# Quad-RS232-1_0-RS232.net
KiCad netlist of a schematic drawn in Altium Designer
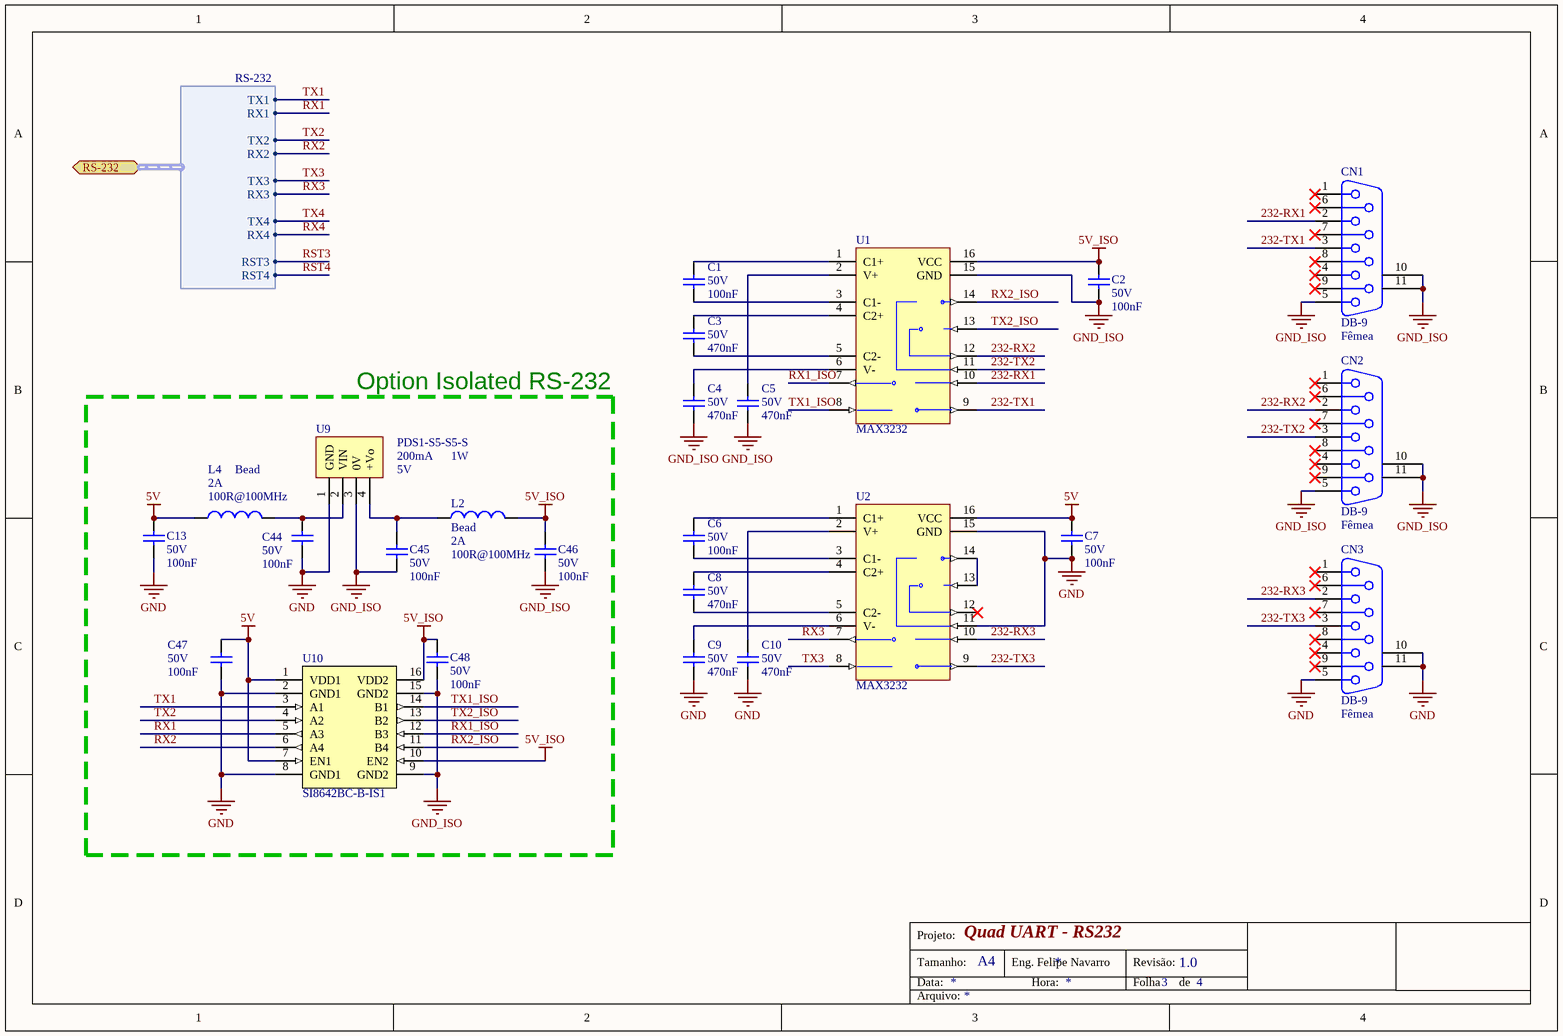
[diagram p0: Quad-RS232-1.0-RS232.SchDoc]

(export (version "E")
  (design (tool "Eeschema 10.0.6"))
  (components
    (comp (ref "C1")
      (value "100nF")
      (footprint "CC0603")
      (description "Capacitor (Semiconductor SIM Model)")
      (fields (field (name "TENSÃO") "50V") (field (name "Comment") "Capacitor Cerâmico"))
      (libsource (lib "NavarroCAP") (part "Cap 1uF 50V 0603 X5R"))
    )
    (comp (ref "C2")
      (value "100nF")
      (footprint "CC0603")
      (description "Capacitor (Semiconductor SIM Model)")
      (fields (field (name "TENSÃO") "50V") (field (name "Comment") "Capacitor Cerâmico"))
      (libsource (lib "NavarroCAP") (part "Cap 100nF 50V 0603 X7R"))
    )
    (comp (ref "C3")
      (value "470nF")
      (footprint "CC0603")
      (description "Capacitor (Semiconductor SIM Model)")
      (fields (field (name "TENSÃO") "50V") (field (name "Comment") "Capacitor Cerâmico"))
      (libsource (lib "NavarroCAP") (part "Cap 1uF 50V 0603 X5R"))
    )
    (comp (ref "C4")
      (value "470nF")
      (footprint "CC0603")
      (description "Capacitor (Semiconductor SIM Model)")
      (fields (field (name "TENSÃO") "50V") (field (name "Comment") "Capacitor Cerâmico"))
      (libsource (lib "NavarroCAP") (part "Cap 1uF 50V 0603 X5R"))
    )
    (comp (ref "C5")
      (value "470nF")
      (footprint "CC0603")
      (description "Capacitor (Semiconductor SIM Model)")
      (fields (field (name "TENSÃO") "50V") (field (name "Comment") "Capacitor Cerâmico"))
      (libsource (lib "NavarroCAP") (part "Cap 1uF 50V 0603 X5R"))
    )
    (comp (ref "C6")
      (value "100nF")
      (footprint "CC0603")
      (description "Capacitor (Semiconductor SIM Model)")
      (fields (field (name "TENSÃO") "50V") (field (name "Comment") "Capacitor Cerâmico"))
      (libsource (lib "NavarroCAP") (part "Cap 1uF 50V 0603 X5R"))
    )
    (comp (ref "C7")
      (value "100nF")
      (footprint "CC0603")
      (description "Capacitor (Semiconductor SIM Model)")
      (fields (field (name "TENSÃO") "50V") (field (name "Comment") "Capacitor Cerâmico"))
      (libsource (lib "NavarroCAP") (part "Cap 100nF 50V 0603 X7R"))
    )
    (comp (ref "C8")
      (value "470nF")
      (footprint "CC0603")
      (description "Capacitor (Semiconductor SIM Model)")
      (fields (field (name "TENSÃO") "50V") (field (name "Comment") "Capacitor Cerâmico"))
      (libsource (lib "NavarroCAP") (part "Cap 1uF 50V 0603 X5R"))
    )
    (comp (ref "C9")
      (value "470nF")
      (footprint "CC0603")
      (description "Capacitor (Semiconductor SIM Model)")
      (fields (field (name "TENSÃO") "50V") (field (name "Comment") "Capacitor Cerâmico"))
      (libsource (lib "NavarroCAP") (part "Cap 1uF 50V 0603 X5R"))
    )
    (comp (ref "C10")
      (value "470nF")
      (footprint "CC0603")
      (description "Capacitor (Semiconductor SIM Model)")
      (fields (field (name "TENSÃO") "50V") (field (name "Comment") "Capacitor Cerâmico"))
      (libsource (lib "NavarroCAP") (part "Cap 1uF 50V 0603 X5R"))
    )
    (comp (ref "C13")
      (value "100nF")
      (footprint "CC0603")
      (description "Capacitor (Semiconductor SIM Model)")
      (fields (field (name "TENSÃO") "50V") (field (name "Comment") "Capacitor Cerâmico"))
      (libsource (lib "NavarroCAP") (part "Cap 100nF 50V 0603 X7R"))
    )
    (comp (ref "C44")
      (value "100nF")
      (footprint "CC0603")
      (description "Capacitor (Semiconductor SIM Model)")
      (fields (field (name "TENSÃO") "50V") (field (name "Comment") "Capacitor Cerâmico"))
      (libsource (lib "NavarroCAP") (part "Cap 100nF 50V 0603 X7R"))
    )
    (comp (ref "C45")
      (value "100nF")
      (footprint "CC0603")
      (description "Capacitor (Semiconductor SIM Model)")
      (fields (field (name "TENSÃO") "50V") (field (name "Comment") "Capacitor Cerâmico"))
      (libsource (lib "NavarroCAP") (part "Cap 100nF 50V 0603 X7R"))
    )
    (comp (ref "C46")
      (value "100nF")
      (footprint "CC0603")
      (description "Capacitor (Semiconductor SIM Model)")
      (fields (field (name "TENSÃO") "50V") (field (name "Comment") "Capacitor Cerâmico"))
      (libsource (lib "NavarroCAP") (part "Cap 100nF 50V 0603 X7R"))
    )
    (comp (ref "C47")
      (value "100nF")
      (footprint "CC0603")
      (description "Capacitor (Semiconductor SIM Model)")
      (fields (field (name "TENSÃO") "50V") (field (name "Comment") "Capacitor Cerâmico"))
      (libsource (lib "NavarroCAP") (part "Cap 100nF 50V 0603 X7R"))
    )
    (comp (ref "C48")
      (value "100nF")
      (footprint "CC0603")
      (description "Capacitor (Semiconductor SIM Model)")
      (fields (field (name "TENSÃO") "50V") (field (name "Comment") "Capacitor Cerâmico"))
      (libsource (lib "NavarroCAP") (part "Cap 100nF 50V 0603 X7R"))
    )
    (comp (ref "CN1")
      (value "DB-9")
      (footprint "CONN DB9-F/H")
      (description "Receptacle Assembly, 9 Position, Right Angle")
      (fields (field (name "ALTIUM_VALUE") "Fêmea"))
      (libsource (lib "NavarroCON") (part "DB-9 Femea"))
    )
    (comp (ref "CN2")
      (value "DB-9")
      (footprint "CONN DB9-F/H")
      (description "Receptacle Assembly, 9 Position, Right Angle")
      (fields (field (name "ALTIUM_VALUE") "Fêmea"))
      (libsource (lib "NavarroCON") (part "DB-9 Femea"))
    )
    (comp (ref "CN3")
      (value "DB-9")
      (footprint "CONN DB9-F/H")
      (description "Receptacle Assembly, 9 Position, Right Angle")
      (fields (field (name "ALTIUM_VALUE") "Fêmea"))
      (libsource (lib "NavarroCON") (part "DB-9 Femea"))
    )
    (comp (ref "L2")
      (value "Bead")
      (footprint "CC0603")
      (fields (field (name "CORRENTE") "2A") (field (name "ALTIUM_VALUE") "100R@100MHz"))
      (libsource (lib "NavarroIND") (part "Bd 100R@100MHz 0603 2A"))
    )
    (comp (ref "L4")
      (value "Bead")
      (footprint "CC0603")
      (fields (field (name "CORRENTE") "2A") (field (name "ALTIUM_VALUE") "100R@100MHz"))
      (libsource (lib "NavarroIND") (part "Bd 100R@100MHz 0603 2A"))
    )
    (comp (ref "U1")
      (value "MAX3232")
      (footprint "SOIC-16N")
      (description "3.0V TO 5.5V, Low-Power, up to 1Mbps, True RS-232 Transceiver Using Four 0.1µF External Capacitor")
      (libsource (lib "Navarro") (part "MAX3232"))
    )
    (comp (ref "U2")
      (value "MAX3232")
      (footprint "SOIC-16N")
      (description "3.0V TO 5.5V, Low-Power, up to 1Mbps, True RS-232 Transceiver Using Four 0.1µF External Capacitor")
      (libsource (lib "Navarro") (part "MAX3232"))
    )
    (comp (ref "U9")
      (value "PDS1-S5-S5-S")
      (footprint "SIP-4N")
      (description "Fonte chaveada isolada")
      (fields (field (name "CORRENTE") "200mA") (field (name "POTÊNCIA") "1W") (field (name "TENSÃO") "5V"))
      (libsource (lib "Navarro") (part "Fonte PDS1-S5-S5-S"))
    )
    (comp (ref "U10")
      (value "SI8642BC-B-IS1")
      (footprint "SOIC-16N")
      (description "LOW-POWER QUAD-CHANNEL DIGITAL ISOLATOR")
      (libsource (lib "Navarro") (part "SI8642"))
    )
  )
  (nets
    (net (code "2") (name "/232-RX1") (class "Default")
      (node (ref "CN1") (pin "2") (pinfunction "2_2") (pintype "passive"))
      (node (ref "U1") (pin "10") (pinfunction "T2IN_10") (pintype "input"))
    )
    (net (code "3") (name "/232-RX2") (class "Default")
      (node (ref "CN2") (pin "2") (pinfunction "2_2") (pintype "passive"))
      (node (ref "U1") (pin "12") (pinfunction "R1OUT_12") (pintype "output"))
    )
    (net (code "4") (name "/232-RX3") (class "Default")
      (node (ref "CN3") (pin "2") (pinfunction "2_2") (pintype "passive"))
      (node (ref "U2") (pin "10") (pinfunction "T2IN_10") (pintype "input"))
    )
    (net (code "5") (name "/232-TX1") (class "Default")
      (node (ref "CN1") (pin "3") (pinfunction "3_3") (pintype "passive"))
      (node (ref "U1") (pin "9") (pinfunction "R2OUT_9") (pintype "output"))
    )
    (net (code "6") (name "/232-TX2") (class "Default")
      (node (ref "CN2") (pin "3") (pinfunction "3_3") (pintype "passive"))
      (node (ref "U1") (pin "11") (pinfunction "T1IN_11") (pintype "input"))
    )
    (net (code "7") (name "/232-TX3") (class "Default")
      (node (ref "CN3") (pin "3") (pinfunction "3_3") (pintype "passive"))
      (node (ref "U2") (pin "9") (pinfunction "R2OUT_9") (pintype "output"))
    )
    (net (code "10") (name "/RX1") (class "Default")
      (node (ref "U10") (pin "5") (pinfunction "A3_5") (pintype "output"))
    )
    (net (code "11") (name "/RX1_ISO") (class "Default")
      (node (ref "U1") (pin "7") (pinfunction "T2OUT_7") (pintype "output"))
      (node (ref "U10") (pin "12") (pinfunction "B3_12") (pintype "input"))
    )
    (net (code "12") (name "/RX2") (class "Default")
      (node (ref "U10") (pin "6") (pinfunction "A4_6") (pintype "output"))
    )
    (net (code "13") (name "/RX2_ISO") (class "Default")
      (node (ref "U1") (pin "14") (pinfunction "T1OUT_14") (pintype "output"))
      (node (ref "U10") (pin "11") (pinfunction "B4_11") (pintype "input"))
    )
    (net (code "14") (name "/RX3") (class "Default")
      (node (ref "U2") (pin "7") (pinfunction "T2OUT_7") (pintype "output"))
    )
    (net (code "16") (name "/TX1") (class "Default")
      (node (ref "U10") (pin "3") (pinfunction "A1_3") (pintype "input"))
    )
    (net (code "17") (name "/TX1_ISO") (class "Default")
      (node (ref "U1") (pin "8") (pinfunction "R2IN_8") (pintype "input"))
      (node (ref "U10") (pin "14") (pinfunction "B1_14") (pintype "output"))
    )
    (net (code "18") (name "/TX2") (class "Default")
      (node (ref "U10") (pin "4") (pinfunction "A2_4") (pintype "input"))
    )
    (net (code "19") (name "/TX2_ISO") (class "Default")
      (node (ref "U1") (pin "13") (pinfunction "R1IN_13") (pintype "input"))
      (node (ref "U10") (pin "13") (pinfunction "B2_13") (pintype "output"))
    )
    (net (code "20") (name "/TX3") (class "Default")
      (node (ref "U2") (pin "8") (pinfunction "R2IN_8") (pintype "input"))
    )
    (net (code "23") (name "5V") (class "Default")
      (node (ref "C13") (pin "2") (pinfunction "2_2") (pintype "passive"))
      (node (ref "C47") (pin "2") (pinfunction "2_2") (pintype "passive"))
      (node (ref "C7") (pin "2") (pinfunction "2_2") (pintype "passive"))
      (node (ref "L4") (pin "1") (pinfunction "1_1") (pintype "passive"))
      (node (ref "U10") (pin "1") (pinfunction "VDD1_1") (pintype "power_in"))
      (node (ref "U10") (pin "7") (pinfunction "EN1_7") (pintype "input"))
      (node (ref "U2") (pin "16") (pinfunction "VCC_16") (pintype "power_in"))
    )
    (net (code "24") (name "5V_ISO") (class "Default")
      (node (ref "C2") (pin "2") (pinfunction "2_2") (pintype "passive"))
      (node (ref "C46") (pin "2") (pinfunction "2_2") (pintype "passive"))
      (node (ref "C48") (pin "2") (pinfunction "2_2") (pintype "passive"))
      (node (ref "L2") (pin "2") (pinfunction "2_2") (pintype "passive"))
      (node (ref "U1") (pin "16") (pinfunction "VCC_16") (pintype "power_in"))
      (node (ref "U10") (pin "10") (pinfunction "EN2_10") (pintype "input"))
      (node (ref "U10") (pin "16") (pinfunction "VDD2_16") (pintype "power_in"))
    )
    (net (code "25") (name "GND") (class "Default")
      (node (ref "C10") (pin "1") (pinfunction "1_1") (pintype "passive"))
      (node (ref "C13") (pin "1") (pinfunction "1_1") (pintype "passive"))
      (node (ref "C44") (pin "1") (pinfunction "1_1") (pintype "passive"))
      (node (ref "C47") (pin "1") (pinfunction "1_1") (pintype "passive"))
      (node (ref "C7") (pin "1") (pinfunction "1_1") (pintype "passive"))
      (node (ref "C9") (pin "1") (pinfunction "1_1") (pintype "passive"))
      (node (ref "CN3") (pin "10") (pinfunction "10_10") (pintype "passive"))
      (node (ref "CN3") (pin "11") (pinfunction "11_11") (pintype "passive"))
      (node (ref "CN3") (pin "5") (pinfunction "5_5") (pintype "passive"))
      (node (ref "U10") (pin "2") (pinfunction "GND1_2") (pintype "power_in"))
      (node (ref "U10") (pin "8") (pinfunction "GND1_8") (pintype "power_in"))
      (node (ref "U2") (pin "11") (pinfunction "T1IN_11") (pintype "input"))
      (node (ref "U2") (pin "15") (pinfunction "GND_15") (pintype "power_in"))
      (node (ref "U9") (pin "1") (pinfunction "GND_1") (pintype "power_in"))
    )
    (net (code "26") (name "GND_ISO") (class "Default")
      (node (ref "C2") (pin "1") (pinfunction "1_1") (pintype "passive"))
      (node (ref "C4") (pin "1") (pinfunction "1_1") (pintype "passive"))
      (node (ref "C45") (pin "1") (pinfunction "1_1") (pintype "passive"))
      (node (ref "C46") (pin "1") (pinfunction "1_1") (pintype "passive"))
      (node (ref "C48") (pin "1") (pinfunction "1_1") (pintype "passive"))
      (node (ref "C5") (pin "1") (pinfunction "1_1") (pintype "passive"))
      (node (ref "CN1") (pin "10") (pinfunction "10_10") (pintype "passive"))
      (node (ref "CN1") (pin "11") (pinfunction "11_11") (pintype "passive"))
      (node (ref "CN1") (pin "5") (pinfunction "5_5") (pintype "passive"))
      (node (ref "CN2") (pin "10") (pinfunction "10_10") (pintype "passive"))
      (node (ref "CN2") (pin "11") (pinfunction "11_11") (pintype "passive"))
      (node (ref "CN2") (pin "5") (pinfunction "5_5") (pintype "passive"))
      (node (ref "U1") (pin "15") (pinfunction "GND_15") (pintype "power_in"))
      (node (ref "U10") (pin "15") (pinfunction "GND2_15") (pintype "power_in"))
      (node (ref "U10") (pin "9") (pinfunction "GND2_9") (pintype "power_in"))
      (node (ref "U9") (pin "3") (pinfunction "0V_3") (pintype "power_in"))
    )
    (net (code "27") (name "Net-(U1-C1+)") (class "Default")
      (node (ref "C1") (pin "2") (pinfunction "2_2") (pintype "passive"))
      (node (ref "U1") (pin "1") (pinfunction "C1+_1") (pintype "passive"))
    )
    (net (code "28") (name "Net-(U1-C1-)") (class "Default")
      (node (ref "C1") (pin "1") (pinfunction "1_1") (pintype "passive"))
      (node (ref "U1") (pin "3") (pinfunction "C1-_3") (pintype "passive"))
    )
    (net (code "29") (name "Net-(U1-C2+)") (class "Default")
      (node (ref "C3") (pin "2") (pinfunction "2_2") (pintype "passive"))
      (node (ref "U1") (pin "4") (pinfunction "C2+_4") (pintype "passive"))
    )
    (net (code "30") (name "Net-(U1-C2-)") (class "Default")
      (node (ref "C3") (pin "1") (pinfunction "1_1") (pintype "passive"))
      (node (ref "U1") (pin "5") (pinfunction "C2-_5") (pintype "passive"))
    )
    (net (code "31") (name "Net-(U1-V+)") (class "Default")
      (node (ref "C5") (pin "2") (pinfunction "2_2") (pintype "passive"))
      (node (ref "U1") (pin "2") (pinfunction "V+_2") (pintype "power_in"))
    )
    (net (code "32") (name "Net-(U1-V-)") (class "Default")
      (node (ref "C4") (pin "2") (pinfunction "2_2") (pintype "passive"))
      (node (ref "U1") (pin "6") (pinfunction "V-_6") (pintype "power_in"))
    )
    (net (code "33") (name "Net-(U2-C1+)") (class "Default")
      (node (ref "C6") (pin "2") (pinfunction "2_2") (pintype "passive"))
      (node (ref "U2") (pin "1") (pinfunction "C1+_1") (pintype "passive"))
    )
    (net (code "34") (name "Net-(U2-C1-)") (class "Default")
      (node (ref "C6") (pin "1") (pinfunction "1_1") (pintype "passive"))
      (node (ref "U2") (pin "3") (pinfunction "C1-_3") (pintype "passive"))
    )
    (net (code "35") (name "Net-(U2-C2+)") (class "Default")
      (node (ref "C8") (pin "2") (pinfunction "2_2") (pintype "passive"))
      (node (ref "U2") (pin "4") (pinfunction "C2+_4") (pintype "passive"))
    )
    (net (code "36") (name "Net-(U2-C2-)") (class "Default")
      (node (ref "C8") (pin "1") (pinfunction "1_1") (pintype "passive"))
      (node (ref "U2") (pin "5") (pinfunction "C2-_5") (pintype "passive"))
    )
    (net (code "37") (name "Net-(U2-R1IN)") (class "Default")
      (node (ref "U2") (pin "13") (pinfunction "R1IN_13") (pintype "input"))
      (node (ref "U2") (pin "14") (pinfunction "T1OUT_14") (pintype "output"))
    )
    (net (code "38") (name "Net-(U2-V+)") (class "Default")
      (node (ref "C10") (pin "2") (pinfunction "2_2") (pintype "passive"))
      (node (ref "U2") (pin "2") (pinfunction "V+_2") (pintype "power_in"))
    )
    (net (code "39") (name "Net-(U2-V-)") (class "Default")
      (node (ref "C9") (pin "2") (pinfunction "2_2") (pintype "passive"))
      (node (ref "U2") (pin "6") (pinfunction "V-_6") (pintype "power_in"))
    )
    (net (code "40") (name "Net-(U9-+Vo)") (class "Default")
      (node (ref "C45") (pin "2") (pinfunction "2_2") (pintype "passive"))
      (node (ref "L2") (pin "1") (pinfunction "1_1") (pintype "passive"))
      (node (ref "U9") (pin "4") (pinfunction "+Vo_4") (pintype "power_in"))
    )
    (net (code "41") (name "Net-(U9-VIN)") (class "Default")
      (node (ref "C44") (pin "2") (pinfunction "2_2") (pintype "passive"))
      (node (ref "L4") (pin "2") (pinfunction "2_2") (pintype "passive"))
      (node (ref "U9") (pin "2") (pinfunction "VIN_2") (pintype "power_in"))
    )
    (net (code "42") (name "unconnected-(CN1-Pad1)") (class "Default")
      (node (ref "CN1") (pin "1") (pinfunction "1_1") (pintype "passive+no_connect"))
    )
    (net (code "43") (name "unconnected-(CN1-Pad4)") (class "Default")
      (node (ref "CN1") (pin "4") (pinfunction "4_4") (pintype "passive+no_connect"))
    )
    (net (code "44") (name "unconnected-(CN1-Pad6)") (class "Default")
      (node (ref "CN1") (pin "6") (pinfunction "6_6") (pintype "passive+no_connect"))
    )
    (net (code "45") (name "unconnected-(CN1-Pad7)") (class "Default")
      (node (ref "CN1") (pin "7") (pinfunction "7_7") (pintype "passive+no_connect"))
    )
    (net (code "46") (name "unconnected-(CN1-Pad8)") (class "Default")
      (node (ref "CN1") (pin "8") (pinfunction "8_8") (pintype "passive+no_connect"))
    )
    (net (code "47") (name "unconnected-(CN1-Pad9)") (class "Default")
      (node (ref "CN1") (pin "9") (pinfunction "9_9") (pintype "passive+no_connect"))
    )
    (net (code "48") (name "unconnected-(CN2-Pad1)") (class "Default")
      (node (ref "CN2") (pin "1") (pinfunction "1_1") (pintype "passive+no_connect"))
    )
    (net (code "49") (name "unconnected-(CN2-Pad4)") (class "Default")
      (node (ref "CN2") (pin "4") (pinfunction "4_4") (pintype "passive+no_connect"))
    )
    (net (code "50") (name "unconnected-(CN2-Pad6)") (class "Default")
      (node (ref "CN2") (pin "6") (pinfunction "6_6") (pintype "passive+no_connect"))
    )
    (net (code "51") (name "unconnected-(CN2-Pad7)") (class "Default")
      (node (ref "CN2") (pin "7") (pinfunction "7_7") (pintype "passive+no_connect"))
    )
    (net (code "52") (name "unconnected-(CN2-Pad8)") (class "Default")
      (node (ref "CN2") (pin "8") (pinfunction "8_8") (pintype "passive+no_connect"))
    )
    (net (code "53") (name "unconnected-(CN2-Pad9)") (class "Default")
      (node (ref "CN2") (pin "9") (pinfunction "9_9") (pintype "passive+no_connect"))
    )
    (net (code "54") (name "unconnected-(CN3-Pad1)") (class "Default")
      (node (ref "CN3") (pin "1") (pinfunction "1_1") (pintype "passive+no_connect"))
    )
    (net (code "55") (name "unconnected-(CN3-Pad4)") (class "Default")
      (node (ref "CN3") (pin "4") (pinfunction "4_4") (pintype "passive+no_connect"))
    )
    (net (code "56") (name "unconnected-(CN3-Pad6)") (class "Default")
      (node (ref "CN3") (pin "6") (pinfunction "6_6") (pintype "passive+no_connect"))
    )
    (net (code "57") (name "unconnected-(CN3-Pad7)") (class "Default")
      (node (ref "CN3") (pin "7") (pinfunction "7_7") (pintype "passive+no_connect"))
    )
    (net (code "58") (name "unconnected-(CN3-Pad8)") (class "Default")
      (node (ref "CN3") (pin "8") (pinfunction "8_8") (pintype "passive+no_connect"))
    )
    (net (code "59") (name "unconnected-(CN3-Pad9)") (class "Default")
      (node (ref "CN3") (pin "9") (pinfunction "9_9") (pintype "passive+no_connect"))
    )
    (net (code "60") (name "unconnected-(U2-R1OUT-Pad12)") (class "Default")
      (node (ref "U2") (pin "12") (pinfunction "R1OUT_12") (pintype "output+no_connect"))
    )
  )
)
